# Programmer.net
KiCad netlist of a schematic drawn in EAGLE
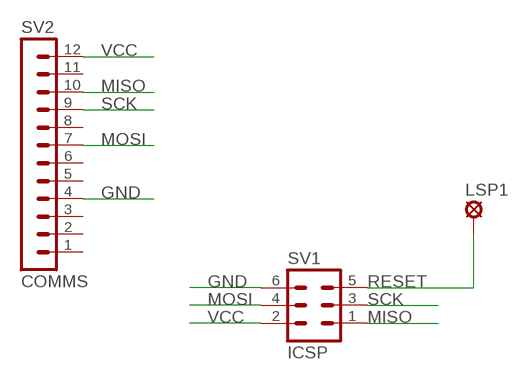
[diagram p0: schematic, sheet 1]

(export (version "E")
  (design (tool "Eeschema 10.0.6"))
  (components
    (comp (ref "LSP1")
      (value "MCS10B")
      (footprint "eagle-import:MCS10B")
      (libsource (lib "eagle-import") (part "MCS10B"))
    )
    (comp (ref "SV1")
      (value "ICSP")
      (footprint "eagle-import:MA03-2")
      (libsource (lib "eagle-import") (part "MA03-2"))
    )
    (comp (ref "SV2")
      (value "COMMS")
      (footprint "eagle-import:MA12-1W")
      (libsource (lib "eagle-import") (part "MA12-1W"))
    )
  )
  (nets
    (net (code "1") (name "/GND") (class "Default")
      (node (ref "SV1") (pin "6") (pinfunction "6_6") (pintype "passive"))
      (node (ref "SV2") (pin "4") (pinfunction "4_4") (pintype "passive"))
    )
    (net (code "2") (name "/MISO") (class "Default")
      (node (ref "SV1") (pin "1") (pinfunction "1_1") (pintype "passive"))
      (node (ref "SV2") (pin "10") (pinfunction "10_10") (pintype "passive"))
    )
    (net (code "3") (name "/MOSI") (class "Default")
      (node (ref "SV1") (pin "4") (pinfunction "4_4") (pintype "passive"))
      (node (ref "SV2") (pin "7") (pinfunction "7_7") (pintype "passive"))
    )
    (net (code "4") (name "/RESET") (class "Default")
      (node (ref "LSP1") (pin "MP") (pinfunction "MP_MP") (pintype "passive"))
      (node (ref "SV1") (pin "5") (pinfunction "5_5") (pintype "passive"))
    )
    (net (code "5") (name "/SCK") (class "Default")
      (node (ref "SV1") (pin "3") (pinfunction "3_3") (pintype "passive"))
      (node (ref "SV2") (pin "9") (pinfunction "9_9") (pintype "passive"))
    )
    (net (code "6") (name "/VCC") (class "Default")
      (node (ref "SV1") (pin "2") (pinfunction "2_2") (pintype "passive"))
      (node (ref "SV2") (pin "12") (pinfunction "12_12") (pintype "passive"))
    )
    (net (code "7") (name "unconnected-(SV2-Pad1)") (class "Default")
      (node (ref "SV2") (pin "1") (pinfunction "1_1") (pintype "passive"))
    )
    (net (code "8") (name "unconnected-(SV2-Pad2)") (class "Default")
      (node (ref "SV2") (pin "2") (pinfunction "2_2") (pintype "passive"))
    )
    (net (code "9") (name "unconnected-(SV2-Pad3)") (class "Default")
      (node (ref "SV2") (pin "3") (pinfunction "3_3") (pintype "passive"))
    )
    (net (code "10") (name "unconnected-(SV2-Pad5)") (class "Default")
      (node (ref "SV2") (pin "5") (pinfunction "5_5") (pintype "passive"))
    )
    (net (code "11") (name "unconnected-(SV2-Pad6)") (class "Default")
      (node (ref "SV2") (pin "6") (pinfunction "6_6") (pintype "passive"))
    )
    (net (code "12") (name "unconnected-(SV2-Pad8)") (class "Default")
      (node (ref "SV2") (pin "8") (pinfunction "8_8") (pintype "passive"))
    )
    (net (code "13") (name "unconnected-(SV2-Pad11)") (class "Default")
      (node (ref "SV2") (pin "11") (pinfunction "11_11") (pintype "passive"))
    )
  )
)
